# protoshield.net
KiCad netlist of a schematic drawn in EAGLE
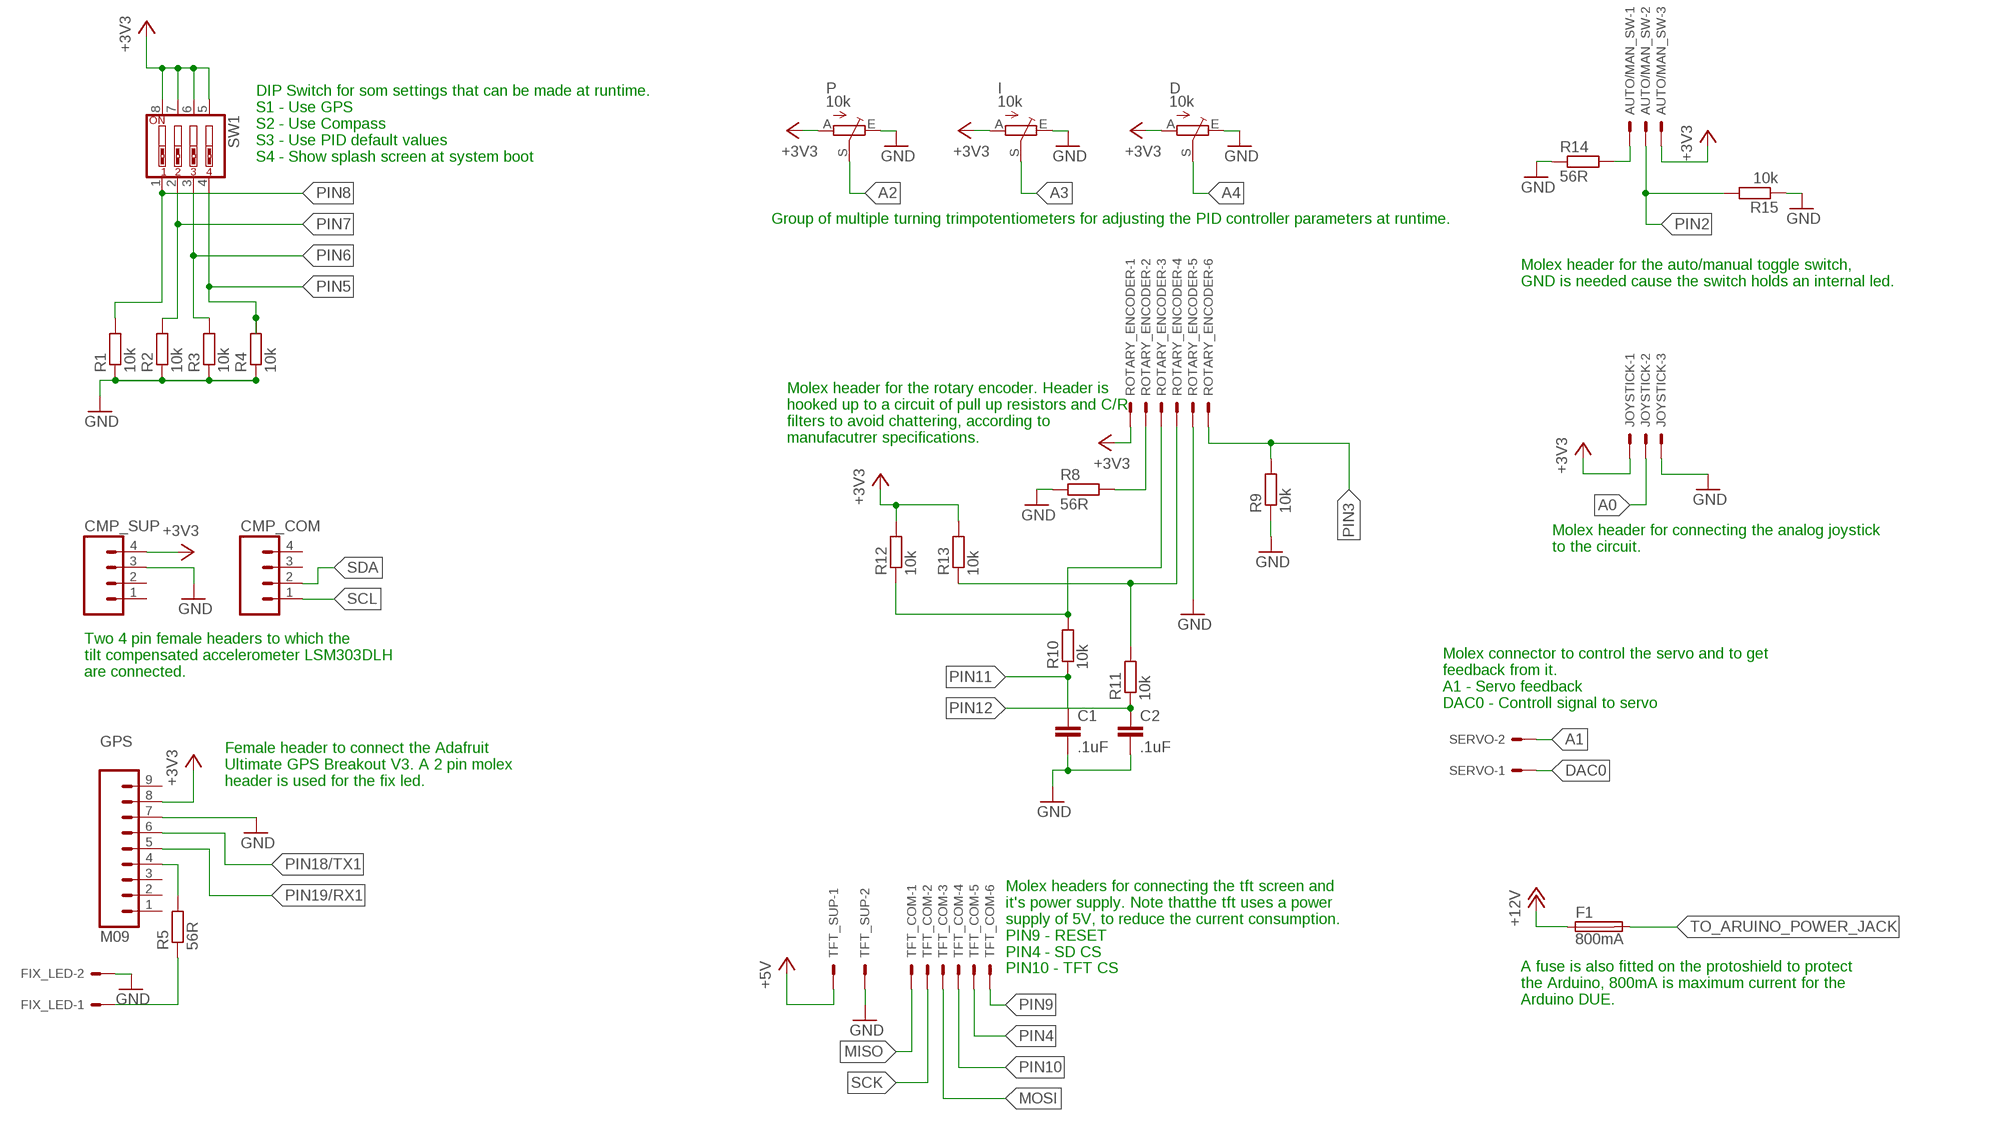
[diagram p0: schematic, sheet 1]

(export (version "E")
  (design (tool "Eeschema 10.0.6"))
  (components
    (comp (ref "AUTO/MAN_SW")
      (value "KK-156-3")
      (footprint "eagle-import:KK-156-3")
      (libsource (lib "eagle-import") (part "KK-156-3"))
    )
    (comp (ref "C1")
      (value ".1uF")
      (footprint "eagle-import:C025-024X044")
      (libsource (lib "eagle-import") (part "C-EU025-024X044"))
    )
    (comp (ref "C2")
      (value ".1uF")
      (footprint "eagle-import:C025-024X044")
      (libsource (lib "eagle-import") (part "C-EU025-024X044"))
    )
    (comp (ref "CMP_COM")
      (value "M04PTH")
      (footprint "eagle-import:1X04")
      (libsource (lib "eagle-import") (part "M04PTH"))
    )
    (comp (ref "CMP_SUP")
      (value "M04PTH")
      (footprint "eagle-import:1X04")
      (libsource (lib "eagle-import") (part "M04PTH"))
    )
    (comp (ref "D")
      (value "10k")
      (footprint "eagle-import:S64W")
      (libsource (lib "eagle-import") (part "TRIM_EU-S64W"))
    )
    (comp (ref "F1")
      (value "800mA")
      (footprint "eagle-import:SH22,5")
      (fields (field (name "MF") "SCHURTER") (field (name "MPN") "0031.8201"))
      (libsource (lib "eagle-import") (part "SH22,5"))
    )
    (comp (ref "FIX_LED")
      (value "KK-156-2")
      (footprint "eagle-import:KK-156-2")
      (libsource (lib "eagle-import") (part "KK-156-2"))
    )
    (comp (ref "GPS")
      (value "M09")
      (footprint "eagle-import:1X09")
      (libsource (lib "eagle-import") (part "M09"))
    )
    (comp (ref "I")
      (value "10k")
      (footprint "eagle-import:S64W")
      (libsource (lib "eagle-import") (part "TRIM_EU-S64W"))
    )
    (comp (ref "JOYSTICK")
      (value "KK-156-3")
      (footprint "eagle-import:KK-156-3")
      (libsource (lib "eagle-import") (part "KK-156-3"))
    )
    (comp (ref "P")
      (value "10k")
      (footprint "eagle-import:S64W")
      (libsource (lib "eagle-import") (part "TRIM_EU-S64W"))
    )
    (comp (ref "R1")
      (value "10k")
      (footprint "eagle-import:0204_7")
      (libsource (lib "eagle-import") (part "R-EU_0204/7"))
    )
    (comp (ref "R2")
      (value "10k")
      (footprint "eagle-import:0204_7")
      (libsource (lib "eagle-import") (part "R-EU_0204/7"))
    )
    (comp (ref "R3")
      (value "10k")
      (footprint "eagle-import:0204_7")
      (libsource (lib "eagle-import") (part "R-EU_0204/7"))
    )
    (comp (ref "R4")
      (value "10k")
      (footprint "eagle-import:0204_7")
      (libsource (lib "eagle-import") (part "R-EU_0204/7"))
    )
    (comp (ref "R5")
      (value "56R")
      (footprint "eagle-import:0204_7")
      (libsource (lib "eagle-import") (part "R-EU_0204/7"))
    )
    (comp (ref "R8")
      (value "56R")
      (footprint "eagle-import:0204_7")
      (libsource (lib "eagle-import") (part "R-EU_0204/7"))
    )
    (comp (ref "R9")
      (value "10k")
      (footprint "eagle-import:0204_7")
      (libsource (lib "eagle-import") (part "R-EU_0204/7"))
    )
    (comp (ref "R10")
      (value "10k")
      (footprint "eagle-import:0204_7")
      (libsource (lib "eagle-import") (part "R-EU_0204/7"))
    )
    (comp (ref "R11")
      (value "10k")
      (footprint "eagle-import:0204_7")
      (libsource (lib "eagle-import") (part "R-EU_0204/7"))
    )
    (comp (ref "R12")
      (value "10k")
      (footprint "eagle-import:0204_7")
      (libsource (lib "eagle-import") (part "R-EU_0204/7"))
    )
    (comp (ref "R13")
      (value "10k")
      (footprint "eagle-import:0204_7")
      (libsource (lib "eagle-import") (part "R-EU_0204/7"))
    )
    (comp (ref "R14")
      (value "56R")
      (footprint "eagle-import:0204_7")
      (libsource (lib "eagle-import") (part "R-EU_0204/7"))
    )
    (comp (ref "R15")
      (value "10k")
      (footprint "eagle-import:0204_7")
      (libsource (lib "eagle-import") (part "R-EU_0204/7"))
    )
    (comp (ref "ROTARY_ENCODER")
      (value "KK-156-6")
      (footprint "eagle-import:KK-156-6")
      (libsource (lib "eagle-import") (part "KK-156-6"))
    )
    (comp (ref "SERVO")
      (value "KK-156-2")
      (footprint "eagle-import:KK-156-2")
      (libsource (lib "eagle-import") (part "KK-156-2"))
    )
    (comp (ref "SW1")
      (value "SW_DIP-4")
      (footprint "eagle-import:EDG-04")
      (libsource (lib "eagle-import") (part "SW_DIP-4"))
    )
    (comp (ref "TFT_COM")
      (value "KK-156-6")
      (footprint "eagle-import:KK-156-6")
      (libsource (lib "eagle-import") (part "KK-156-6"))
    )
    (comp (ref "TFT_SUP")
      (value "KK-156-2")
      (footprint "eagle-import:KK-156-2")
      (libsource (lib "eagle-import") (part "KK-156-2"))
    )
  )
  (nets
    (net (code "1") (name "+3V3") (class "Default")
      (node (ref "AUTO/MAN_SW") (pin "3") (pinfunction "S_3") (pintype "passive"))
      (node (ref "CMP_SUP") (pin "4") (pinfunction "4_4") (pintype "passive"))
      (node (ref "D") (pin "A") (pinfunction "A_A") (pintype "passive"))
      (node (ref "GPS") (pin "8") (pinfunction "8_8") (pintype "passive"))
      (node (ref "I") (pin "A") (pinfunction "A_A") (pintype "passive"))
      (node (ref "JOYSTICK") (pin "1") (pinfunction "S_1") (pintype "passive"))
      (node (ref "P") (pin "A") (pinfunction "A_A") (pintype "passive"))
      (node (ref "R12") (pin "2") (pinfunction "2_2") (pintype "passive"))
      (node (ref "R13") (pin "2") (pinfunction "2_2") (pintype "passive"))
      (node (ref "ROTARY_ENCODER") (pin "1") (pinfunction "S_1") (pintype "passive"))
      (node (ref "SW1") (pin "5") (pinfunction "5_5") (pintype "passive"))
      (node (ref "SW1") (pin "6") (pinfunction "6_6") (pintype "passive"))
      (node (ref "SW1") (pin "7") (pinfunction "7_7") (pintype "passive"))
      (node (ref "SW1") (pin "8") (pinfunction "8_8") (pintype "passive"))
    )
    (net (code "2") (name "+5V") (class "Default")
      (node (ref "TFT_SUP") (pin "1") (pinfunction "S_1") (pintype "passive"))
    )
    (net (code "3") (name "+12V") (class "Default")
      (node (ref "F1") (pin "1") (pinfunction "1_1") (pintype "passive"))
    )
    (net (code "4") (name "A0") (class "Default")
      (node (ref "JOYSTICK") (pin "2") (pinfunction "S_2") (pintype "passive"))
    )
    (net (code "5") (name "A1") (class "Default")
      (node (ref "SERVO") (pin "2") (pinfunction "S_2") (pintype "passive"))
    )
    (net (code "6") (name "A2") (class "Default")
      (node (ref "P") (pin "S") (pinfunction "S_S") (pintype "passive"))
    )
    (net (code "7") (name "A3") (class "Default")
      (node (ref "I") (pin "S") (pinfunction "S_S") (pintype "passive"))
    )
    (net (code "8") (name "A4") (class "Default")
      (node (ref "D") (pin "S") (pinfunction "S_S") (pintype "passive"))
    )
    (net (code "9") (name "DAC0") (class "Default")
      (node (ref "SERVO") (pin "1") (pinfunction "S_1") (pintype "passive"))
    )
    (net (code "10") (name "GND") (class "Default")
      (node (ref "C1") (pin "2") (pinfunction "2_2") (pintype "passive"))
      (node (ref "C2") (pin "2") (pinfunction "2_2") (pintype "passive"))
      (node (ref "CMP_SUP") (pin "3") (pinfunction "3_3") (pintype "passive"))
      (node (ref "D") (pin "E") (pinfunction "E_E") (pintype "passive"))
      (node (ref "FIX_LED") (pin "2") (pinfunction "S_2") (pintype "passive"))
      (node (ref "GPS") (pin "7") (pinfunction "7_7") (pintype "passive"))
      (node (ref "I") (pin "E") (pinfunction "E_E") (pintype "passive"))
      (node (ref "JOYSTICK") (pin "3") (pinfunction "S_3") (pintype "passive"))
      (node (ref "P") (pin "E") (pinfunction "E_E") (pintype "passive"))
      (node (ref "R1") (pin "1") (pinfunction "1_1") (pintype "passive"))
      (node (ref "R14") (pin "1") (pinfunction "1_1") (pintype "passive"))
      (node (ref "R15") (pin "1") (pinfunction "1_1") (pintype "passive"))
      (node (ref "R2") (pin "1") (pinfunction "1_1") (pintype "passive"))
      (node (ref "R3") (pin "1") (pinfunction "1_1") (pintype "passive"))
      (node (ref "R4") (pin "1") (pinfunction "1_1") (pintype "passive"))
      (node (ref "R8") (pin "1") (pinfunction "1_1") (pintype "passive"))
      (node (ref "R9") (pin "1") (pinfunction "1_1") (pintype "passive"))
      (node (ref "ROTARY_ENCODER") (pin "5") (pinfunction "S_5") (pintype "passive"))
      (node (ref "TFT_SUP") (pin "2") (pinfunction "S_2") (pintype "passive"))
    )
    (net (code "11") (name "MISO") (class "Default")
      (node (ref "TFT_COM") (pin "1") (pinfunction "S_1") (pintype "passive"))
    )
    (net (code "12") (name "MOSI") (class "Default")
      (node (ref "TFT_COM") (pin "3") (pinfunction "S_3") (pintype "passive"))
    )
    (net (code "13") (name "Net-(AUTO/MAN_SWA-S)") (class "Default")
      (node (ref "AUTO/MAN_SW") (pin "1") (pinfunction "S_1") (pintype "passive"))
      (node (ref "R14") (pin "2") (pinfunction "2_2") (pintype "passive"))
    )
    (net (code "14") (name "Net-(FIX_LEDA-S)") (class "Default")
      (node (ref "FIX_LED") (pin "1") (pinfunction "S_1") (pintype "passive"))
      (node (ref "R5") (pin "1") (pinfunction "1_1") (pintype "passive"))
    )
    (net (code "15") (name "Net-(GPS-Pad4)") (class "Default")
      (node (ref "GPS") (pin "4") (pinfunction "4_4") (pintype "passive"))
      (node (ref "R5") (pin "2") (pinfunction "2_2") (pintype "passive"))
    )
    (net (code "16") (name "Net-(ROTARY_ENCODERB-S)") (class "Default")
      (node (ref "R8") (pin "2") (pinfunction "2_2") (pintype "passive"))
      (node (ref "ROTARY_ENCODER") (pin "2") (pinfunction "S_2") (pintype "passive"))
    )
    (net (code "17") (name "Net-(ROTARY_ENCODERC-S)") (class "Default")
      (node (ref "R10") (pin "2") (pinfunction "2_2") (pintype "passive"))
      (node (ref "R12") (pin "1") (pinfunction "1_1") (pintype "passive"))
      (node (ref "ROTARY_ENCODER") (pin "3") (pinfunction "S_3") (pintype "passive"))
    )
    (net (code "18") (name "Net-(ROTARY_ENCODERD-S)") (class "Default")
      (node (ref "R11") (pin "2") (pinfunction "2_2") (pintype "passive"))
      (node (ref "R13") (pin "1") (pinfunction "1_1") (pintype "passive"))
      (node (ref "ROTARY_ENCODER") (pin "4") (pinfunction "S_4") (pintype "passive"))
    )
    (net (code "19") (name "PIN2") (class "Default")
      (node (ref "AUTO/MAN_SW") (pin "2") (pinfunction "S_2") (pintype "passive"))
      (node (ref "R15") (pin "2") (pinfunction "2_2") (pintype "passive"))
    )
    (net (code "20") (name "PIN3") (class "Default")
      (node (ref "R9") (pin "2") (pinfunction "2_2") (pintype "passive"))
      (node (ref "ROTARY_ENCODER") (pin "6") (pinfunction "S_6") (pintype "passive"))
    )
    (net (code "21") (name "PIN4") (class "Default")
      (node (ref "TFT_COM") (pin "5") (pinfunction "S_5") (pintype "passive"))
    )
    (net (code "22") (name "PIN5") (class "Default")
      (node (ref "R4") (pin "2") (pinfunction "2_2") (pintype "passive"))
      (node (ref "SW1") (pin "4") (pinfunction "4_4") (pintype "passive"))
    )
    (net (code "23") (name "PIN6") (class "Default")
      (node (ref "R3") (pin "2") (pinfunction "2_2") (pintype "passive"))
      (node (ref "SW1") (pin "3") (pinfunction "3_3") (pintype "passive"))
    )
    (net (code "24") (name "PIN7") (class "Default")
      (node (ref "R2") (pin "2") (pinfunction "2_2") (pintype "passive"))
      (node (ref "SW1") (pin "2") (pinfunction "2_2") (pintype "passive"))
    )
    (net (code "25") (name "PIN8") (class "Default")
      (node (ref "R1") (pin "2") (pinfunction "2_2") (pintype "passive"))
      (node (ref "SW1") (pin "1") (pinfunction "1_1") (pintype "passive"))
    )
    (net (code "26") (name "PIN9") (class "Default")
      (node (ref "TFT_COM") (pin "6") (pinfunction "S_6") (pintype "passive"))
    )
    (net (code "27") (name "PIN10") (class "Default")
      (node (ref "TFT_COM") (pin "4") (pinfunction "S_4") (pintype "passive"))
    )
    (net (code "28") (name "PIN11") (class "Default")
      (node (ref "C1") (pin "1") (pinfunction "1_1") (pintype "passive"))
      (node (ref "R10") (pin "1") (pinfunction "1_1") (pintype "passive"))
    )
    (net (code "29") (name "PIN12") (class "Default")
      (node (ref "C2") (pin "1") (pinfunction "1_1") (pintype "passive"))
      (node (ref "R11") (pin "1") (pinfunction "1_1") (pintype "passive"))
    )
    (net (code "30") (name "PIN18{slash}TX1") (class "Default")
      (node (ref "GPS") (pin "6") (pinfunction "6_6") (pintype "passive"))
    )
    (net (code "31") (name "PIN19{slash}RX1") (class "Default")
      (node (ref "GPS") (pin "5") (pinfunction "5_5") (pintype "passive"))
    )
    (net (code "32") (name "SCK") (class "Default")
      (node (ref "TFT_COM") (pin "2") (pinfunction "S_2") (pintype "passive"))
    )
    (net (code "33") (name "SCL") (class "Default")
      (node (ref "CMP_COM") (pin "1") (pinfunction "1_1") (pintype "passive"))
    )
    (net (code "34") (name "SDA") (class "Default")
      (node (ref "CMP_COM") (pin "2") (pinfunction "2_2") (pintype "passive"))
    )
    (net (code "35") (name "TO_ARUINO_POWER_JACK") (class "Default")
      (node (ref "F1") (pin "2") (pinfunction "2_2") (pintype "passive"))
    )
    (net (code "36") (name "unconnected-(CMP_COM-Pad3)") (class "Default")
      (node (ref "CMP_COM") (pin "3") (pinfunction "3_3") (pintype "passive"))
    )
    (net (code "37") (name "unconnected-(CMP_COM-Pad4)") (class "Default")
      (node (ref "CMP_COM") (pin "4") (pinfunction "4_4") (pintype "passive"))
    )
    (net (code "38") (name "unconnected-(CMP_SUP-Pad1)") (class "Default")
      (node (ref "CMP_SUP") (pin "1") (pinfunction "1_1") (pintype "passive"))
    )
    (net (code "39") (name "unconnected-(CMP_SUP-Pad2)") (class "Default")
      (node (ref "CMP_SUP") (pin "2") (pinfunction "2_2") (pintype "passive"))
    )
    (net (code "40") (name "unconnected-(GPS-Pad1)") (class "Default")
      (node (ref "GPS") (pin "1") (pinfunction "1_1") (pintype "passive"))
    )
    (net (code "41") (name "unconnected-(GPS-Pad2)") (class "Default")
      (node (ref "GPS") (pin "2") (pinfunction "2_2") (pintype "passive"))
    )
    (net (code "42") (name "unconnected-(GPS-Pad3)") (class "Default")
      (node (ref "GPS") (pin "3") (pinfunction "3_3") (pintype "passive"))
    )
    (net (code "43") (name "unconnected-(GPS-Pad9)") (class "Default")
      (node (ref "GPS") (pin "9") (pinfunction "9_9") (pintype "passive"))
    )
  )
)
